# OC_PROT.net
KiCad netlist of a schematic drawn in Altium Designer
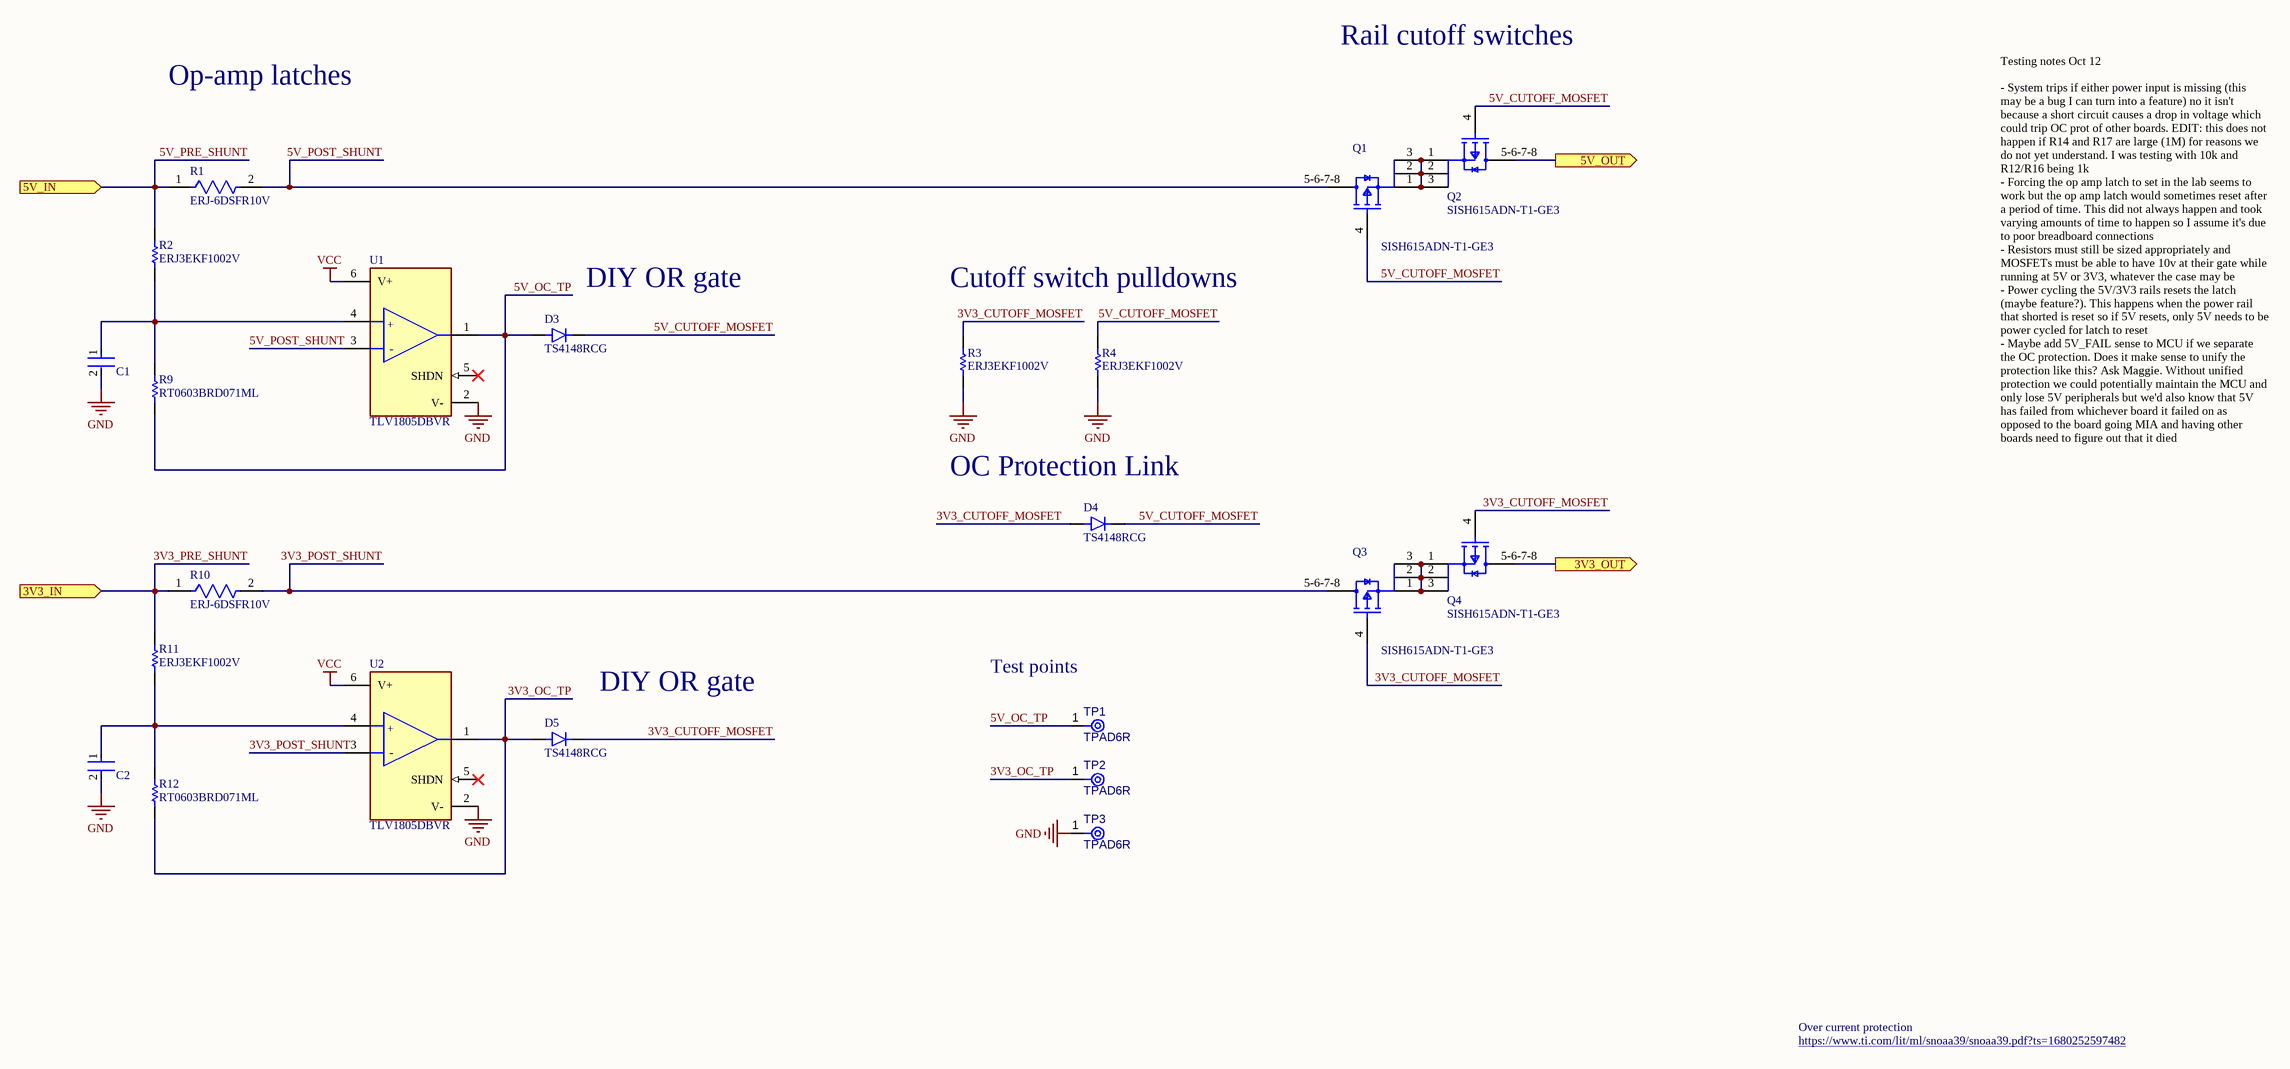
[diagram p0: OC_PROT.SchDoc]

(export (version "E")
  (design (tool "Eeschema 10.0.6"))
  (components
    (comp (ref "C1")
      (value "C0402C104K8PACTU")
      (footprint "FP-C0402-BB-MFG")
      (description "CAP CER 0.1UF 10V X5R 0402")
      (fields (field (name "MANUFACTURER") "Kemet") (field (name "TOLERANCE") "0.1"))
      (libsource (lib "Altium Content Vault") (part "b4654b650e69147ec39a6b967a45e02"))
    )
    (comp (ref "C2")
      (value "C0402C104K8PACTU")
      (footprint "FP-C0402-BB-MFG")
      (description "CAP CER 0.1UF 10V X5R 0402")
      (fields (field (name "MANUFACTURER") "Kemet") (field (name "TOLERANCE") "0.1"))
      (libsource (lib "Altium Content Vault") (part "b4654b650e69147ec39a6b967a45e02"))
    )
    (comp (ref "D3")
      (value "TS4148RCG")
      (footprint "TS4148RCG-Footprint-1")
      (description "SMD Si-Diode 75V 100mA 0603")
      (libsource (lib "uORocketry Hardware") (part "TS4148RCG"))
    )
    (comp (ref "D4")
      (value "TS4148RCG")
      (footprint "TS4148RCG-Footprint-1")
      (description "SMD Si-Diode 75V 100mA 0603")
      (libsource (lib "uORocketry Hardware") (part "TS4148RCG"))
    )
    (comp (ref "D5")
      (value "TS4148RCG")
      (footprint "TS4148RCG-Footprint-1")
      (description "SMD Si-Diode 75V 100mA 0603")
      (libsource (lib "uORocketry Hardware") (part "TS4148RCG"))
    )
    (comp (ref "Q1")
      (value "SISH615ADN-T1-GE3")
      (footprint "SISH615ADN-T1-GE3-Footprint-1")
      (description "Trans MOSFET P-CH 20V 22.1A 8-Pin PowerPAK 1212 EP T/R")
      (libsource (lib "uORocketry Hardware") (part "SISH615ADN-T1-GE3-Symbol-1"))
    )
    (comp (ref "Q2")
      (value "SISH615ADN-T1-GE3")
      (footprint "SISH615ADN-T1-GE3-Footprint-1")
      (description "Trans MOSFET P-CH 20V 22.1A 8-Pin PowerPAK 1212 EP T/R")
      (libsource (lib "uORocketry Hardware") (part "SISH615ADN-T1-GE3-Symbol-1"))
    )
    (comp (ref "Q3")
      (value "SISH615ADN-T1-GE3")
      (footprint "SISH615ADN-T1-GE3-Footprint-1")
      (description "Trans MOSFET P-CH 20V 22.1A 8-Pin PowerPAK 1212 EP T/R")
      (libsource (lib "uORocketry Hardware") (part "SISH615ADN-T1-GE3-Symbol-1"))
    )
    (comp (ref "Q4")
      (value "SISH615ADN-T1-GE3")
      (footprint "SISH615ADN-T1-GE3-Footprint-1")
      (description "Trans MOSFET P-CH 20V 22.1A 8-Pin PowerPAK 1212 EP T/R")
      (libsource (lib "uORocketry Hardware") (part "SISH615ADN-T1-GE3-Symbol-1"))
    )
    (comp (ref "R1")
      (value "ERJ-6DSFR10V")
      (footprint "FP-ERJ6D-MFG")
      (description "RES 0.1 OHM 1% 1/2W 0805")
      (fields (field (name "TOLERANCE") "1%"))
      (libsource (lib "Altium Content Vault") (part "1029c3af85768c4190bb7ad29bc67b5"))
    )
    (comp (ref "R2")
      (value "ERJ3EKF1002V")
      (footprint "RESC1609X55X30LL15T15")
      (description "Chip Resistor, 10 KOhm, +/- 1%, 0.1 W, -55 to 155 degC, 0603 (1608 Metric), RoHS, Tape and Reel")
      (fields (field (name "TOLERANCE") "1%") (field (name "MANUFACTURER") "Panasonic"))
      (libsource (lib "Altium Content Vault") (part "RES-2"))
    )
    (comp (ref "R3")
      (value "ERJ3EKF1002V")
      (footprint "RESC1609X55X30LL15T15")
      (description "Chip Resistor, 10 KOhm, +/- 1%, 0.1 W, -55 to 155 degC, 0603 (1608 Metric), RoHS, Tape and Reel")
      (fields (field (name "TOLERANCE") "1%") (field (name "MANUFACTURER") "Panasonic"))
      (libsource (lib "Altium Content Vault") (part "RES-2"))
    )
    (comp (ref "R4")
      (value "ERJ3EKF1002V")
      (footprint "RESC1609X55X30LL15T15")
      (description "Chip Resistor, 10 KOhm, +/- 1%, 0.1 W, -55 to 155 degC, 0603 (1608 Metric), RoHS, Tape and Reel")
      (fields (field (name "TOLERANCE") "1%") (field (name "MANUFACTURER") "Panasonic"))
      (libsource (lib "Altium Content Vault") (part "RES-2"))
    )
    (comp (ref "R9")
      (value "RT0603BRD071ML")
      (footprint "RESC1608X55X30NL20T20")
      (fields (field (name "MANUFACTURER") "Panasonic") (field (name "PART NUMBER") "ERA-3AEB163V"))
      (libsource (lib "Altium Content Vault") (part "RES"))
    )
    (comp (ref "R10")
      (value "ERJ-6DSFR10V")
      (footprint "FP-ERJ6D-MFG")
      (description "RES 0.1 OHM 1% 1/2W 0805")
      (fields (field (name "TOLERANCE") "1%"))
      (libsource (lib "Altium Content Vault") (part "1029c3af85768c4190bb7ad29bc67b5"))
    )
    (comp (ref "R11")
      (value "ERJ3EKF1002V")
      (footprint "RESC1609X55X30LL15T15")
      (description "Chip Resistor, 10 KOhm, +/- 1%, 0.1 W, -55 to 155 degC, 0603 (1608 Metric), RoHS, Tape and Reel")
      (fields (field (name "TOLERANCE") "1%") (field (name "MANUFACTURER") "Panasonic"))
      (libsource (lib "Altium Content Vault") (part "RES-2"))
    )
    (comp (ref "R12")
      (value "RT0603BRD071ML")
      (footprint "RESC1608X55X30NL20T20")
      (fields (field (name "MANUFACTURER") "Panasonic") (field (name "PART NUMBER") "ERA-3AEB163V"))
      (libsource (lib "Altium Content Vault") (part "RES"))
    )
    (comp (ref "TP1")
      (value "TPAD6R")
      (footprint "TP06R")
      (description "0.6mm round")
      (libsource (lib "uORocketry Hardware") (part "CMP-001-0001-4"))
    )
    (comp (ref "TP2")
      (value "TPAD6R")
      (footprint "TP06R")
      (description "0.6mm round")
      (libsource (lib "uORocketry Hardware") (part "CMP-001-0001-4"))
    )
    (comp (ref "TP3")
      (value "TPAD6R")
      (footprint "TP06R")
      (description "0.6mm round")
      (libsource (lib "uORocketry Hardware") (part "CMP-001-0001-4"))
    )
    (comp (ref "U1")
      (value "TLV1805DBVR")
      (footprint "FP-DBV0006A-IPC_C")
      (description "40V, RAIL-TO-RAIL INPUT, PUSH-PU")
      (libsource (lib "Altium Content Vault") (part "c7aa3bc3dbf0dc8b0b0354779bd1228"))
    )
    (comp (ref "U2")
      (value "TLV1805DBVR")
      (footprint "FP-DBV0006A-IPC_C")
      (description "40V, RAIL-TO-RAIL INPUT, PUSH-PU")
      (libsource (lib "Altium Content Vault") (part "c7aa3bc3dbf0dc8b0b0354779bd1228"))
    )
  )
  (nets
    (net (code "1") (name "/3V3_CUTOFF_MOSFET") (class "Default")
      (node (ref "D4") (pin "A") (pinfunction "A_A") (pintype "passive"))
      (node (ref "D5") (pin "C") (pinfunction "K_C") (pintype "passive"))
      (node (ref "Q3") (pin "4") (pinfunction "G_4") (pintype "passive"))
      (node (ref "Q4") (pin "4") (pinfunction "G_4") (pintype "passive"))
      (node (ref "R3") (pin "2") (pinfunction "2_2") (pintype "passive"))
    )
    (net (code "2") (name "/3V3_OC_TP") (class "Default")
      (node (ref "D5") (pin "A") (pinfunction "A_A") (pintype "passive"))
      (node (ref "R12") (pin "1") (pinfunction "1_1") (pintype "passive"))
      (node (ref "TP2") (pin "1") (pinfunction "TP_1") (pintype "passive"))
      (node (ref "U2") (pin "1") (pinfunction "OUT_1") (pintype "passive"))
    )
    (net (code "3") (name "/3V3_OUT") (class "Default")
      (node (ref "Q4") (pin "5-6-7-8") (pinfunction "D_5-6-7-8") (pintype "passive"))
    )
    (net (code "4") (name "/3V3_POST_SHUNT") (class "Default")
      (node (ref "Q3") (pin "5-6-7-8") (pinfunction "D_5-6-7-8") (pintype "passive"))
      (node (ref "R10") (pin "2") (pinfunction "2_2") (pintype "passive"))
      (node (ref "U2") (pin "3") (pinfunction "-IN_3") (pintype "tri_state"))
    )
    (net (code "5") (name "/3V3_PRE_SHUNT") (class "Default")
      (node (ref "R10") (pin "1") (pinfunction "1_1") (pintype "passive"))
      (node (ref "R11") (pin "2") (pinfunction "2_2") (pintype "passive"))
    )
    (net (code "6") (name "/5V_CUTOFF_MOSFET") (class "Default")
      (node (ref "D3") (pin "C") (pinfunction "K_C") (pintype "passive"))
      (node (ref "D4") (pin "C") (pinfunction "K_C") (pintype "passive"))
      (node (ref "Q1") (pin "4") (pinfunction "G_4") (pintype "passive"))
      (node (ref "Q2") (pin "4") (pinfunction "G_4") (pintype "passive"))
      (node (ref "R4") (pin "2") (pinfunction "2_2") (pintype "passive"))
    )
    (net (code "7") (name "/5V_OC_TP") (class "Default")
      (node (ref "D3") (pin "A") (pinfunction "A_A") (pintype "passive"))
      (node (ref "R9") (pin "1") (pinfunction "1_1") (pintype "passive"))
      (node (ref "TP1") (pin "1") (pinfunction "TP_1") (pintype "passive"))
      (node (ref "U1") (pin "1") (pinfunction "OUT_1") (pintype "passive"))
    )
    (net (code "8") (name "/5V_OUT") (class "Default")
      (node (ref "Q2") (pin "5-6-7-8") (pinfunction "D_5-6-7-8") (pintype "passive"))
    )
    (net (code "9") (name "/5V_POST_SHUNT") (class "Default")
      (node (ref "Q1") (pin "5-6-7-8") (pinfunction "D_5-6-7-8") (pintype "passive"))
      (node (ref "R1") (pin "2") (pinfunction "2_2") (pintype "passive"))
      (node (ref "U1") (pin "3") (pinfunction "-IN_3") (pintype "tri_state"))
    )
    (net (code "10") (name "/5V_PRE_SHUNT") (class "Default")
      (node (ref "R1") (pin "1") (pinfunction "1_1") (pintype "passive"))
      (node (ref "R2") (pin "2") (pinfunction "2_2") (pintype "passive"))
    )
    (net (code "11") (name "GND") (class "Default")
      (node (ref "C1") (pin "2") (pinfunction "2_2") (pintype "passive"))
      (node (ref "C2") (pin "2") (pinfunction "2_2") (pintype "passive"))
      (node (ref "R3") (pin "1") (pinfunction "1_1") (pintype "passive"))
      (node (ref "R4") (pin "1") (pinfunction "1_1") (pintype "passive"))
      (node (ref "TP3") (pin "1") (pinfunction "TP_1") (pintype "passive"))
      (node (ref "U1") (pin "2") (pinfunction "V-_2") (pintype "power_in"))
      (node (ref "U2") (pin "2") (pinfunction "V-_2") (pintype "power_in"))
    )
    (net (code "12") (name "Net-(Q1-S-Pad1)") (class "Default")
      (node (ref "Q1") (pin "1") (pinfunction "S_1") (pintype "passive"))
      (node (ref "Q1") (pin "2") (pinfunction "S_2") (pintype "passive"))
      (node (ref "Q1") (pin "3") (pinfunction "S_3") (pintype "passive"))
      (node (ref "Q2") (pin "1") (pinfunction "S_1") (pintype "passive"))
      (node (ref "Q2") (pin "2") (pinfunction "S_2") (pintype "passive"))
      (node (ref "Q2") (pin "3") (pinfunction "S_3") (pintype "passive"))
    )
    (net (code "13") (name "Net-(Q3-S-Pad1)") (class "Default")
      (node (ref "Q3") (pin "1") (pinfunction "S_1") (pintype "passive"))
      (node (ref "Q3") (pin "2") (pinfunction "S_2") (pintype "passive"))
      (node (ref "Q3") (pin "3") (pinfunction "S_3") (pintype "passive"))
      (node (ref "Q4") (pin "1") (pinfunction "S_1") (pintype "passive"))
      (node (ref "Q4") (pin "2") (pinfunction "S_2") (pintype "passive"))
      (node (ref "Q4") (pin "3") (pinfunction "S_3") (pintype "passive"))
    )
    (net (code "14") (name "Net-(U1-+IN)") (class "Default")
      (node (ref "C1") (pin "1") (pinfunction "1_1") (pintype "passive"))
      (node (ref "R2") (pin "1") (pinfunction "1_1") (pintype "passive"))
      (node (ref "R9") (pin "2") (pinfunction "2_2") (pintype "passive"))
      (node (ref "U1") (pin "4") (pinfunction "+IN_4") (pintype "tri_state"))
    )
    (net (code "15") (name "Net-(U2-+IN)") (class "Default")
      (node (ref "C2") (pin "1") (pinfunction "1_1") (pintype "passive"))
      (node (ref "R11") (pin "1") (pinfunction "1_1") (pintype "passive"))
      (node (ref "R12") (pin "2") (pinfunction "2_2") (pintype "passive"))
      (node (ref "U2") (pin "4") (pinfunction "+IN_4") (pintype "tri_state"))
    )
    (net (code "16") (name "VCC") (class "Default")
      (node (ref "U1") (pin "6") (pinfunction "V+_6") (pintype "power_in"))
      (node (ref "U2") (pin "6") (pinfunction "V+_6") (pintype "power_in"))
    )
    (net (code "17") (name "unconnected-(U1-SHDN-Pad5)") (class "Default")
      (node (ref "U1") (pin "5") (pinfunction "SHDN_5") (pintype "input+no_connect"))
    )
    (net (code "18") (name "unconnected-(U2-SHDN-Pad5)") (class "Default")
      (node (ref "U2") (pin "5") (pinfunction "SHDN_5") (pintype "input+no_connect"))
    )
  )
)
